# board.net
KiCad netlist of a schematic drawn in EAGLE
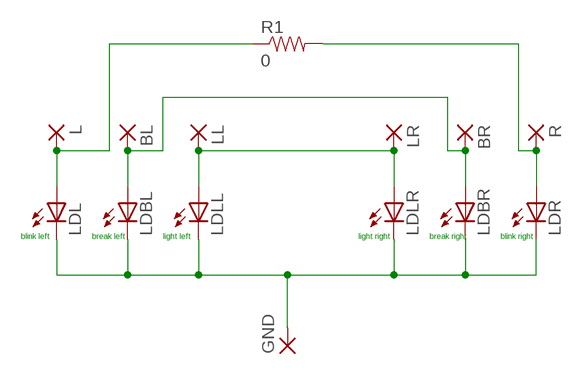
[diagram p0: schematic, sheet 1]

(export (version "E")
  (design (tool "Eeschema 10.0.6"))
  (components
    (comp (ref "BL")
      (value "SMD2")
      (footprint "eagle-import:SMD1,27-2,54")
      (libsource (lib "eagle-import") (part "SMD2"))
    )
    (comp (ref "BR")
      (value "SMD2")
      (footprint "eagle-import:SMD1,27-2,54")
      (libsource (lib "eagle-import") (part "SMD2"))
    )
    (comp (ref "GND")
      (value "SMD2")
      (footprint "eagle-import:SMD1,27-2,54")
      (libsource (lib "eagle-import") (part "SMD2"))
    )
    (comp (ref "L")
      (value "SMD2")
      (footprint "eagle-import:SMD1,27-2,54")
      (libsource (lib "eagle-import") (part "SMD2"))
    )
    (comp (ref "LDBL")
      (value "LEDCHIP-LED0603")
      (footprint "eagle-import:CHIP-LED0603")
      (libsource (lib "eagle-import") (part "LEDCHIP-LED0603"))
    )
    (comp (ref "LDBR")
      (value "LEDCHIP-LED0603")
      (footprint "eagle-import:CHIP-LED0603")
      (libsource (lib "eagle-import") (part "LEDCHIP-LED0603"))
    )
    (comp (ref "LDL")
      (value "LEDCHIP-LED0603")
      (footprint "eagle-import:CHIP-LED0603")
      (libsource (lib "eagle-import") (part "LEDCHIP-LED0603"))
    )
    (comp (ref "LDLL")
      (value "LEDCHIP-LED0603")
      (footprint "eagle-import:CHIP-LED0603")
      (libsource (lib "eagle-import") (part "LEDCHIP-LED0603"))
    )
    (comp (ref "LDLR")
      (value "LEDCHIP-LED0603")
      (footprint "eagle-import:CHIP-LED0603")
      (libsource (lib "eagle-import") (part "LEDCHIP-LED0603"))
    )
    (comp (ref "LDR")
      (value "LEDCHIP-LED0603")
      (footprint "eagle-import:CHIP-LED0603")
      (libsource (lib "eagle-import") (part "LEDCHIP-LED0603"))
    )
    (comp (ref "LL")
      (value "SMD2")
      (footprint "eagle-import:SMD1,27-2,54")
      (libsource (lib "eagle-import") (part "SMD2"))
    )
    (comp (ref "LR")
      (value "SMD2")
      (footprint "eagle-import:SMD1,27-2,54")
      (libsource (lib "eagle-import") (part "SMD2"))
    )
    (comp (ref "R")
      (value "SMD2")
      (footprint "eagle-import:SMD1,27-2,54")
      (libsource (lib "eagle-import") (part "SMD2"))
    )
    (comp (ref "R1")
      (value "0")
      (footprint "eagle-import:0603")
      (libsource (lib "eagle-import") (part "1.5KOHM-1/10W-1%(0603)"))
    )
  )
  (nets
    (net (code "1") (name "Net-(BL-P)") (class "Default")
      (node (ref "BL") (pin "1") (pinfunction "P_1") (pintype "passive"))
      (node (ref "BR") (pin "1") (pinfunction "P_1") (pintype "passive"))
      (node (ref "LDBL") (pin "A") (pinfunction "A_A") (pintype "passive"))
      (node (ref "LDBR") (pin "A") (pinfunction "A_A") (pintype "passive"))
    )
    (net (code "2") (name "Net-(GND-P)") (class "Default")
      (node (ref "GND") (pin "1") (pinfunction "P_1") (pintype "passive"))
      (node (ref "LDBL") (pin "C") (pinfunction "C_C") (pintype "passive"))
      (node (ref "LDBR") (pin "C") (pinfunction "C_C") (pintype "passive"))
      (node (ref "LDL") (pin "C") (pinfunction "C_C") (pintype "passive"))
      (node (ref "LDLL") (pin "C") (pinfunction "C_C") (pintype "passive"))
      (node (ref "LDLR") (pin "C") (pinfunction "C_C") (pintype "passive"))
      (node (ref "LDR") (pin "C") (pinfunction "C_C") (pintype "passive"))
    )
    (net (code "3") (name "Net-(L-P)") (class "Default")
      (node (ref "L") (pin "1") (pinfunction "P_1") (pintype "passive"))
      (node (ref "LDL") (pin "A") (pinfunction "A_A") (pintype "passive"))
      (node (ref "R1") (pin "1") (pinfunction "1_1") (pintype "passive"))
    )
    (net (code "4") (name "Net-(LL-P)") (class "Default")
      (node (ref "LDLL") (pin "A") (pinfunction "A_A") (pintype "passive"))
      (node (ref "LDLR") (pin "A") (pinfunction "A_A") (pintype "passive"))
      (node (ref "LL") (pin "1") (pinfunction "P_1") (pintype "passive"))
      (node (ref "LR") (pin "1") (pinfunction "P_1") (pintype "passive"))
    )
    (net (code "5") (name "Net-(R-P)") (class "Default")
      (node (ref "LDR") (pin "A") (pinfunction "A_A") (pintype "passive"))
      (node (ref "R") (pin "1") (pinfunction "P_1") (pintype "passive"))
      (node (ref "R1") (pin "2") (pinfunction "2_2") (pintype "passive"))
    )
  )
)
